# can-bus_trancseiver.net
KiCad netlist of a schematic drawn in EAGLE
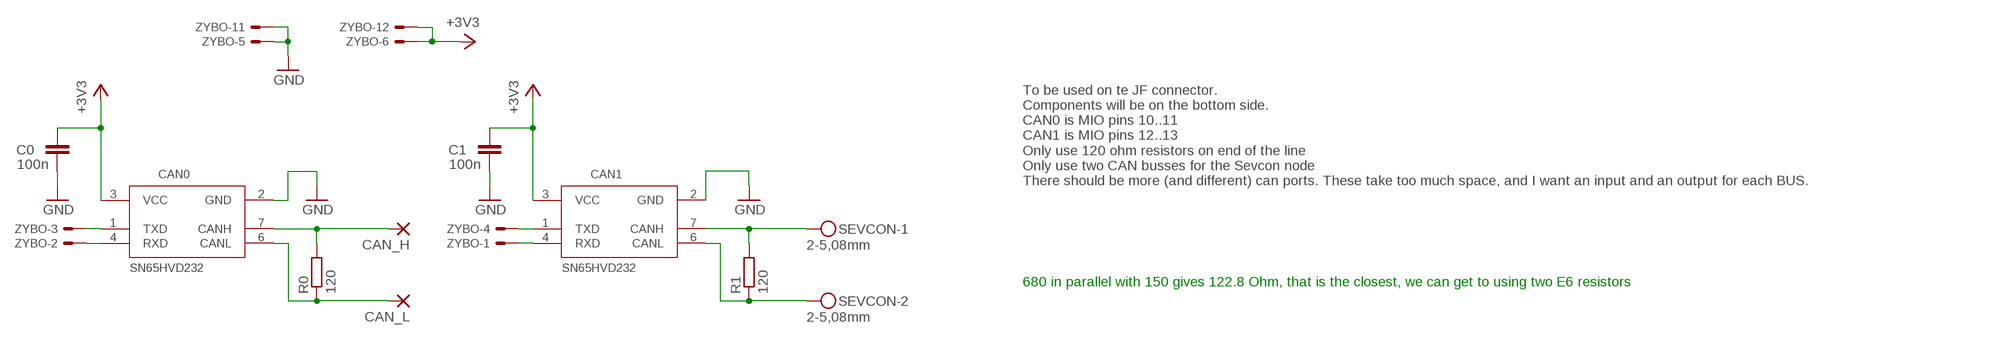
[diagram p0: schematic, sheet 1]

(export (version "E")
  (design (tool "Eeschema 10.0.6"))
  (components
    (comp (ref "C0")
      (value "100n")
      (footprint "eagle-import:C0805K")
      (libsource (lib "eagle-import") (part "C-EUC0805K"))
    )
    (comp (ref "C1")
      (value "100n")
      (footprint "eagle-import:C0805K")
      (libsource (lib "eagle-import") (part "C-EUC0805K"))
    )
    (comp (ref "CAN0")
      (value "SN65HVD232")
      (footprint "eagle-import:SO08")
      (libsource (lib "eagle-import") (part "SN65HVD232"))
    )
    (comp (ref "CAN1")
      (value "SN65HVD232")
      (footprint "eagle-import:SO08")
      (libsource (lib "eagle-import") (part "SN65HVD232"))
    )
    (comp (ref "CAN_H")
      (value "1,6/0,8")
      (footprint "eagle-import:1,6_0,8")
      (libsource (lib "eagle-import") (part "1,6/0,8"))
    )
    (comp (ref "CAN_L")
      (value "1,6/0,8")
      (footprint "eagle-import:1,6_0,8")
      (libsource (lib "eagle-import") (part "1,6/0,8"))
    )
    (comp (ref "R0")
      (value "120")
      (footprint "eagle-import:R0805")
      (libsource (lib "eagle-import") (part "R-EU_R0805"))
    )
    (comp (ref "R1")
      (value "120")
      (footprint "eagle-import:R0805")
      (libsource (lib "eagle-import") (part "R-EU_R0805"))
    )
    (comp (ref "SEVCON")
      (value "2-5,08mm")
      (footprint "eagle-import:MKDSN1,5_2-5,08")
      (libsource (lib "eagle-import") (part "MKDSN1,5/2-5,08"))
    )
    (comp (ref "ZYBO")
      (value "PMOD12")
      (footprint "eagle-import:PMOD12")
      (libsource (lib "eagle-import") (part "PMOD12"))
    )
  )
  (nets
    (net (code "1") (name "+3V3") (class "Default")
      (node (ref "C0") (pin "1") (pinfunction "1_1") (pintype "passive"))
      (node (ref "C1") (pin "1") (pinfunction "1_1") (pintype "passive"))
      (node (ref "CAN0") (pin "3") (pinfunction "VCC_3") (pintype "power_in"))
      (node (ref "CAN1") (pin "3") (pinfunction "VCC_3") (pintype "power_in"))
      (node (ref "ZYBO") (pin "12") (pinfunction "S_12") (pintype "passive"))
      (node (ref "ZYBO") (pin "6") (pinfunction "S_6") (pintype "passive"))
    )
    (net (code "2") (name "GND") (class "Default")
      (node (ref "C0") (pin "2") (pinfunction "2_2") (pintype "passive"))
      (node (ref "C1") (pin "2") (pinfunction "2_2") (pintype "passive"))
      (node (ref "CAN0") (pin "2") (pinfunction "GND_2") (pintype "power_in"))
      (node (ref "CAN1") (pin "2") (pinfunction "GND_2") (pintype "power_in"))
      (node (ref "ZYBO") (pin "11") (pinfunction "S_11") (pintype "passive"))
      (node (ref "ZYBO") (pin "5") (pinfunction "S_5") (pintype "passive"))
    )
    (net (code "3") (name "Net-(CAN0-CANH)") (class "Default")
      (node (ref "CAN0") (pin "7") (pinfunction "CANH_7") (pintype "bidirectional"))
      (node (ref "CAN_H") (pin "1") (pinfunction "P_1") (pintype "passive"))
      (node (ref "R0") (pin "2") (pinfunction "2_2") (pintype "passive"))
    )
    (net (code "4") (name "Net-(CAN0-CANL)") (class "Default")
      (node (ref "CAN0") (pin "6") (pinfunction "CANL_6") (pintype "bidirectional"))
      (node (ref "CAN_L") (pin "1") (pinfunction "P_1") (pintype "passive"))
      (node (ref "R0") (pin "1") (pinfunction "1_1") (pintype "passive"))
    )
    (net (code "5") (name "Net-(CAN0-RXD)") (class "Default")
      (node (ref "CAN0") (pin "4") (pinfunction "RXD_4") (pintype "output"))
      (node (ref "ZYBO") (pin "2") (pinfunction "S_2") (pintype "passive"))
    )
    (net (code "6") (name "Net-(CAN0-TXD)") (class "Default")
      (node (ref "CAN0") (pin "1") (pinfunction "TXD_1") (pintype "input"))
      (node (ref "ZYBO") (pin "3") (pinfunction "S_3") (pintype "passive"))
    )
    (net (code "7") (name "Net-(CAN1-CANH)") (class "Default")
      (node (ref "CAN1") (pin "7") (pinfunction "CANH_7") (pintype "bidirectional"))
      (node (ref "R1") (pin "2") (pinfunction "2_2") (pintype "passive"))
      (node (ref "SEVCON") (pin "1") (pinfunction "KL_1") (pintype "passive"))
    )
    (net (code "8") (name "Net-(CAN1-CANL)") (class "Default")
      (node (ref "CAN1") (pin "6") (pinfunction "CANL_6") (pintype "bidirectional"))
      (node (ref "R1") (pin "1") (pinfunction "1_1") (pintype "passive"))
      (node (ref "SEVCON") (pin "2") (pinfunction "KL_2") (pintype "passive"))
    )
    (net (code "9") (name "Net-(CAN1-RXD)") (class "Default")
      (node (ref "CAN1") (pin "4") (pinfunction "RXD_4") (pintype "output"))
      (node (ref "ZYBO") (pin "1") (pinfunction "S_1") (pintype "passive"))
    )
    (net (code "10") (name "Net-(CAN1-TXD)") (class "Default")
      (node (ref "CAN1") (pin "1") (pinfunction "TXD_1") (pintype "input"))
      (node (ref "ZYBO") (pin "4") (pinfunction "S_4") (pintype "passive"))
    )
  )
)
